# powerSource.net
KiCad netlist of a schematic drawn in Altium Designer
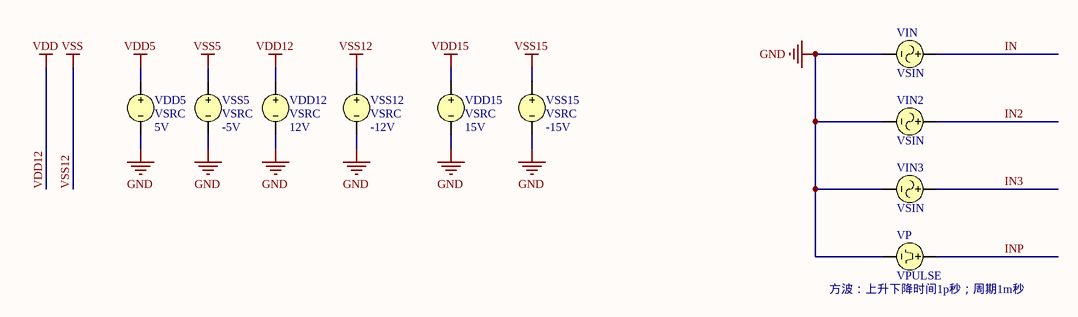
[diagram p0: powerSource.SchDoc]

(export (version "E")
  (design (tool "Eeschema 10.0.6"))
  (components
    (comp (ref "VDD5")
      (value "VSRC")
      (description "Voltage Source")
      (fields (field (name "ALTIUM_VALUE") "5V") (field (name "PUBLISHER") "Altium Limited"))
      (libsource (lib "Simulation Sources") (part "VSRC"))
    )
    (comp (ref "VDD12")
      (value "VSRC")
      (description "Voltage Source")
      (fields (field (name "ALTIUM_VALUE") "12V") (field (name "PUBLISHER") "Altium Limited"))
      (libsource (lib "Simulation Sources") (part "VSRC"))
    )
    (comp (ref "VDD15")
      (value "VSRC")
      (description "Voltage Source")
      (fields (field (name "ALTIUM_VALUE") "15V") (field (name "PUBLISHER") "Altium Limited"))
      (libsource (lib "Simulation Sources") (part "VSRC"))
    )
    (comp (ref "VIN")
      (value "VSIN")
      (description "Sinusoidal Voltage Source")
      (fields (field (name "PUBLISHER") "Altium Limited"))
      (libsource (lib "Simulation Sources") (part "VSIN"))
    )
    (comp (ref "VIN2")
      (value "VSIN")
      (description "Sinusoidal Voltage Source")
      (fields (field (name "PUBLISHER") "Altium Limited"))
      (libsource (lib "Simulation Sources") (part "VSIN"))
    )
    (comp (ref "VIN3")
      (value "VSIN")
      (description "Sinusoidal Voltage Source")
      (fields (field (name "PUBLISHER") "Altium Limited"))
      (libsource (lib "Simulation Sources") (part "VSIN"))
    )
    (comp (ref "VP")
      (value "VPULSE")
      (description "Pulse Voltage Source")
      (fields (field (name "PUBLISHER") "Altium Limited"))
      (libsource (lib "Simulation Sources") (part "VPULSE"))
    )
    (comp (ref "VSS5")
      (value "VSRC")
      (description "Voltage Source")
      (fields (field (name "ALTIUM_VALUE") "-5V") (field (name "PUBLISHER") "Altium Limited"))
      (libsource (lib "Simulation Sources") (part "VSRC"))
    )
    (comp (ref "VSS12")
      (value "VSRC")
      (description "Voltage Source")
      (fields (field (name "ALTIUM_VALUE") "-12V") (field (name "PUBLISHER") "Altium Limited"))
      (libsource (lib "Simulation Sources") (part "VSRC"))
    )
    (comp (ref "VSS15")
      (value "VSRC")
      (description "Voltage Source")
      (fields (field (name "ALTIUM_VALUE") "-15V") (field (name "PUBLISHER") "Altium Limited"))
      (libsource (lib "Simulation Sources") (part "VSRC"))
    )
  )
  (nets
    (net (code "1") (name "/IN") (class "Default")
      (node (ref "VIN") (pin "1") (pinfunction "1_1") (pintype "passive"))
    )
    (net (code "2") (name "/IN2") (class "Default")
      (node (ref "VIN2") (pin "1") (pinfunction "1_1") (pintype "passive"))
    )
    (net (code "3") (name "/IN3") (class "Default")
      (node (ref "VIN3") (pin "1") (pinfunction "1_1") (pintype "passive"))
    )
    (net (code "4") (name "/INP") (class "Default")
      (node (ref "VP") (pin "1") (pinfunction "1_1") (pintype "passive"))
    )
    (net (code "5") (name "GND") (class "Default")
      (node (ref "VDD12") (pin "2") (pinfunction "2_2") (pintype "passive"))
      (node (ref "VDD15") (pin "2") (pinfunction "2_2") (pintype "passive"))
      (node (ref "VDD5") (pin "2") (pinfunction "2_2") (pintype "passive"))
      (node (ref "VIN") (pin "2") (pinfunction "2_2") (pintype "passive"))
      (node (ref "VIN2") (pin "2") (pinfunction "2_2") (pintype "passive"))
      (node (ref "VIN3") (pin "2") (pinfunction "2_2") (pintype "passive"))
      (node (ref "VP") (pin "2") (pinfunction "2_2") (pintype "passive"))
      (node (ref "VSS12") (pin "2") (pinfunction "2_2") (pintype "passive"))
      (node (ref "VSS15") (pin "2") (pinfunction "2_2") (pintype "passive"))
      (node (ref "VSS5") (pin "2") (pinfunction "2_2") (pintype "passive"))
    )
    (net (code "6") (name "VDD") (class "Default")
      (node (ref "VDD12") (pin "1") (pinfunction "1_1") (pintype "passive"))
    )
    (net (code "7") (name "VDD5") (class "Default")
      (node (ref "VDD5") (pin "1") (pinfunction "1_1") (pintype "passive"))
    )
    (net (code "8") (name "VDD15") (class "Default")
      (node (ref "VDD15") (pin "1") (pinfunction "1_1") (pintype "passive"))
    )
    (net (code "9") (name "VSS") (class "Default")
      (node (ref "VSS12") (pin "1") (pinfunction "1_1") (pintype "passive"))
    )
    (net (code "10") (name "VSS5") (class "Default")
      (node (ref "VSS5") (pin "1") (pinfunction "1_1") (pintype "passive"))
    )
    (net (code "11") (name "VSS15") (class "Default")
      (node (ref "VSS15") (pin "1") (pinfunction "1_1") (pintype "passive"))
    )
  )
)
